# Sheet1_XL6009.net
KiCad netlist of a schematic drawn in Altium Designer
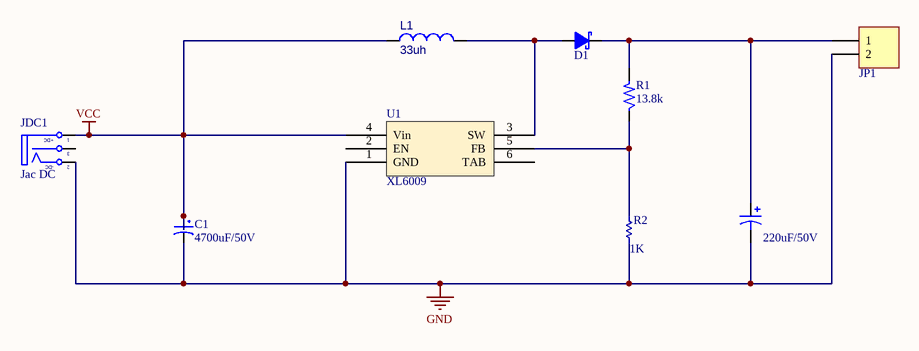
[diagram p0: Sheet1_XL6009.SchDoc]

(export (version "E")
  (design (tool "Eeschema 10.0.6"))
  (components
    (comp (ref "C1")
      (value "4700uF/50V")
      (footprint "CP4/8.5")
      (description "Cap 4700uF/50V")
      (libsource (lib "syhaunguyen") (part "CP7"))
    )
    (comp (ref "C22")
      (value "220uF/50V")
      (footprint "CP2/5")
      (description "Polarized Capacitor (Surface Mount)")
      (fields (field (name "Comment") "Cap Pol3") (field (name "PUBLISHER") "Altium Limited"))
      (libsource (lib "syhaunguyen") (part "Cap Pol3"))
    )
    (comp (ref "D1")
      (value "Diode  Schottky 1N5819")
      (footprint "DO-214AC")
      (description "Diode 1A")
      (libsource (lib "My library altium") (part "Diode  Schottky 1N5819"))
    )
    (comp (ref "JDC1")
      (value "Jac DC")
      (footprint "DC-IN")
      (description "Jac DC input")
      (libsource (lib "syhaunguyen") (part "DCIN"))
    )
    (comp (ref "JP1")
      (value "Header 2_1")
      (footprint "HED2")
      (description "Header, 2-Pin")
      (fields (field (name "MANUFACTURER") "Generic Components"))
      (libsource (lib "syhaunguyen") (part "Header 2_1"))
    )
    (comp (ref "L1")
      (value "33uh")
      (footprint "IND_COILCRAFT_LPS4018")
      (description "Inductor shielded 120uH 300mA LPS4018 SMD")
      (fields (field (name "TOLERANCE") "±20%"))
      (libsource (lib "My library altium") (part "INDC_120u_LPS4018"))
    )
    (comp (ref "R1")
      (value "13.8k")
      (footprint "SM-RES-1206")
      (description "Resistor 1/4W")
      (libsource (lib "syhaunguyen") (part "R"))
    )
    (comp (ref "R2")
      (value "1K")
      (footprint "RES 1/2W")
      (fields (field (name "Comment") "Resistor 1/4W"))
      (libsource (lib "PIF_C16_lib") (part "RES"))
    )
    (comp (ref "U1")
      (value "XL6009")
      (footprint "LM2596")
      (description "SMD")
      (libsource (lib "buck&boost (1)") (part "XL6009"))
    )
  )
  (nets
    (net (code "1") (name "GND") (class "Default")
      (node (ref "C1") (pin "2") (pinfunction "2_2") (pintype "passive"))
      (node (ref "C22") (pin "2") (pinfunction "2_2") (pintype "passive"))
      (node (ref "JDC1") (pin "2") (pinfunction "TN_2") (pintype "passive"))
      (node (ref "JP1") (pin "2") (pinfunction "2_2") (pintype "passive"))
      (node (ref "R2") (pin "1") (pintype "passive"))
      (node (ref "U1") (pin "1") (pinfunction "GND_1") (pintype "passive"))
    )
    (net (code "2") (name "Net-(C22-Pad1)") (class "Default")
      (node (ref "C22") (pin "1") (pinfunction "1_1") (pintype "passive"))
      (node (ref "D1") (pin "K") (pinfunction "K_K") (pintype "passive"))
      (node (ref "JP1") (pin "1") (pinfunction "1_1") (pintype "passive"))
      (node (ref "R1") (pin "2") (pinfunction "2_2") (pintype "passive"))
    )
    (net (code "3") (name "Net-(U1-FB)") (class "Default")
      (node (ref "R1") (pin "1") (pinfunction "1_1") (pintype "passive"))
      (node (ref "R2") (pin "2") (pintype "passive"))
      (node (ref "U1") (pin "5") (pinfunction "FB_5") (pintype "passive"))
    )
    (net (code "4") (name "Net-(U1-SW)") (class "Default")
      (node (ref "D1") (pin "A") (pinfunction "A_A") (pintype "passive"))
      (node (ref "L1") (pin "2") (pinfunction "2_2") (pintype "passive"))
      (node (ref "U1") (pin "3") (pinfunction "SW_3") (pintype "passive"))
    )
    (net (code "5") (name "VCC") (class "Default")
      (node (ref "C1") (pin "1") (pinfunction "1_1") (pintype "passive"))
      (node (ref "JDC1") (pin "1") (pinfunction "T_1") (pintype "passive"))
      (node (ref "L1") (pin "1") (pinfunction "1_1") (pintype "passive"))
      (node (ref "U1") (pin "4") (pinfunction "Vin_4") (pintype "passive"))
    )
    (net (code "6") (name "unconnected-(JDC1-S-Pad3)") (class "Default")
      (node (ref "JDC1") (pin "3") (pinfunction "S_3") (pintype "power_in"))
    )
    (net (code "7") (name "unconnected-(U1-EN-Pad2)") (class "Default")
      (node (ref "U1") (pin "2") (pinfunction "EN_2") (pintype "passive"))
    )
    (net (code "8") (name "unconnected-(U1-TAB-Pad6)") (class "Default")
      (node (ref "U1") (pin "6") (pinfunction "TAB_6") (pintype "passive"))
    )
  )
)
